# PGA.net
KiCad netlist of a schematic drawn in Altium Designer
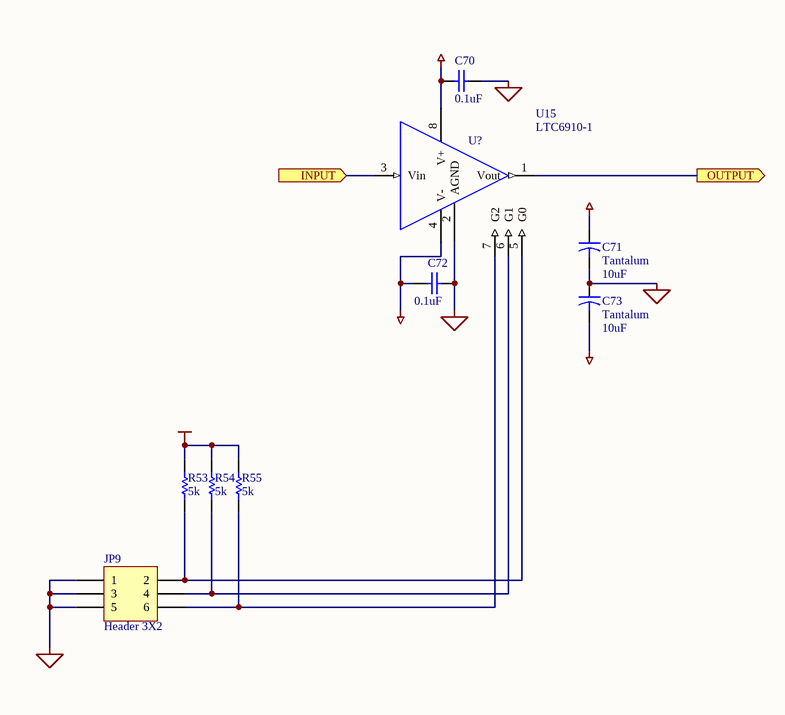
[diagram p0: PGA.SCHDOC]

(export (version "E")
  (design (tool "Eeschema 10.0.6"))
  (components
    (comp (ref "C70")
      (value "0.1uF")
      (footprint "CC1608-0603")
      (description "Capacitor")
      (fields
        (field (name "MANUFACTURER") "Generic Components")
        (field (name "Comment") "Cap")
        (field (name "PUBLISHER") "Altium Limited")
      )
      (libsource (lib "Miscellaneous Devices") (part "Cap"))
    )
    (comp (ref "C71")
      (value "Tantalum")
      (footprint "TC3216-1206")
      (description "Capacitor")
      (fields
        (field (name "MANUFACTURER") "Generic Components")
        (field (name "ALTIUM_VALUE") "10uF")
        (field (name "PUBLISHER") "Altium Limited")
      )
      (libsource (lib "Miscellaneous Devices") (part "Cap2"))
    )
    (comp (ref "C72")
      (value "0.1uF")
      (footprint "CC1608-0603")
      (description "Capacitor")
      (fields
        (field (name "MANUFACTURER") "Generic Components")
        (field (name "Comment") "Cap")
        (field (name "PUBLISHER") "Altium Limited")
      )
      (libsource (lib "Miscellaneous Devices") (part "Cap"))
    )
    (comp (ref "C73")
      (value "Tantalum")
      (footprint "TC3216-1206")
      (description "Capacitor")
      (fields
        (field (name "MANUFACTURER") "Generic Components")
        (field (name "ALTIUM_VALUE") "10uF")
        (field (name "PUBLISHER") "Altium Limited")
      )
      (libsource (lib "Miscellaneous Devices") (part "Cap2"))
    )
    (comp (ref "JP9")
      (value "Header 3X2")
      (footprint "HDR2X3")
      (description "Header, 3-Pin, Dual row")
      (fields (field (name "MANUFACTURER") "Generic Components") (field (name "PUBLISHER") "Altium Limited"))
      (libsource (lib "Miscellaneous Connectors") (part "Header 3X2"))
    )
    (comp (ref "R53")
      (value "5k")
      (footprint "CC2012-0805")
      (description "Resistor")
      (fields
        (field (name "MANUFACTURER") "Generic Components")
        (field (name "Comment") "Res1")
        (field (name "PUBLISHER") "Altium Limited")
      )
      (libsource (lib "Miscellaneous Devices") (part "Res1"))
    )
    (comp (ref "R54")
      (value "5k")
      (footprint "CC2012-0805")
      (description "Resistor")
      (fields
        (field (name "MANUFACTURER") "Generic Components")
        (field (name "Comment") "Res1")
        (field (name "PUBLISHER") "Altium Limited")
      )
      (libsource (lib "Miscellaneous Devices") (part "Res1"))
    )
    (comp (ref "R55")
      (value "5k")
      (footprint "CC2012-0805")
      (description "Resistor")
      (fields
        (field (name "MANUFACTURER") "Generic Components")
        (field (name "Comment") "Res1")
        (field (name "PUBLISHER") "Altium Limited")
      )
      (libsource (lib "Miscellaneous Devices") (part "Res1"))
    )
    (comp (ref "U15")
      (value "LTC6910-1")
      (footprint "TSOT-23-8")
      (description "LTI Digitally Controlled Programmabe Gain Amp")
      (libsource (lib "My devices") (part "LTC6910-2"))
    )
  )
  (nets
    (net (code "1") (name "/INPUT") (class "Default")
      (node (ref "U15") (pin "3") (pinfunction "Vin_3") (pintype "input"))
    )
    (net (code "2") (name "/OUTPUT") (class "Default")
      (node (ref "U15") (pin "1") (pinfunction "Vout_1") (pintype "output"))
    )
    (net (code "3") (name "AGND") (class "Default")
      (node (ref "C70") (pin "2") (pinfunction "2_2") (pintype "passive"))
      (node (ref "C71") (pin "2") (pinfunction "2_2") (pintype "passive"))
      (node (ref "C72") (pin "1") (pinfunction "1_1") (pintype "passive"))
      (node (ref "C73") (pin "1") (pinfunction "1_1") (pintype "passive"))
      (node (ref "JP9") (pin "1") (pinfunction "1_1") (pintype "passive"))
      (node (ref "JP9") (pin "3") (pinfunction "3_3") (pintype "passive"))
      (node (ref "JP9") (pin "5") (pinfunction "5_5") (pintype "passive"))
      (node (ref "U15") (pin "2") (pinfunction "AGND_2") (pintype "power_in"))
    )
    (net (code "4") (name "AVDD") (class "Default")
      (node (ref "C70") (pin "1") (pinfunction "1_1") (pintype "passive"))
      (node (ref "C71") (pin "1") (pinfunction "1_1") (pintype "passive"))
      (node (ref "R53") (pin "2") (pinfunction "2_2") (pintype "passive"))
      (node (ref "R54") (pin "2") (pinfunction "2_2") (pintype "passive"))
      (node (ref "R55") (pin "2") (pinfunction "2_2") (pintype "passive"))
      (node (ref "U15") (pin "8") (pinfunction "V+_8") (pintype "power_in"))
    )
    (net (code "5") (name "AVSS") (class "Default")
      (node (ref "C72") (pin "2") (pinfunction "2_2") (pintype "passive"))
      (node (ref "C73") (pin "2") (pinfunction "2_2") (pintype "passive"))
      (node (ref "U15") (pin "4") (pinfunction "V-_4") (pintype "power_in"))
    )
    (net (code "6") (name "Net-(U15-G0)") (class "Default")
      (node (ref "JP9") (pin "2") (pinfunction "2_2") (pintype "passive"))
      (node (ref "R53") (pin "1") (pinfunction "1_1") (pintype "passive"))
      (node (ref "U15") (pin "5") (pinfunction "G0_5") (pintype "input"))
    )
    (net (code "7") (name "Net-(U15-G1)") (class "Default")
      (node (ref "JP9") (pin "4") (pinfunction "4_4") (pintype "passive"))
      (node (ref "R54") (pin "1") (pinfunction "1_1") (pintype "passive"))
      (node (ref "U15") (pin "6") (pinfunction "G1_6") (pintype "input"))
    )
    (net (code "8") (name "Net-(U15-G2)") (class "Default")
      (node (ref "JP9") (pin "6") (pinfunction "6_6") (pintype "passive"))
      (node (ref "R55") (pin "1") (pinfunction "1_1") (pintype "passive"))
      (node (ref "U15") (pin "7") (pinfunction "G2_7") (pintype "input"))
    )
  )
)
